# servo_receiver.net
KiCad netlist of a schematic drawn in Altium Designer
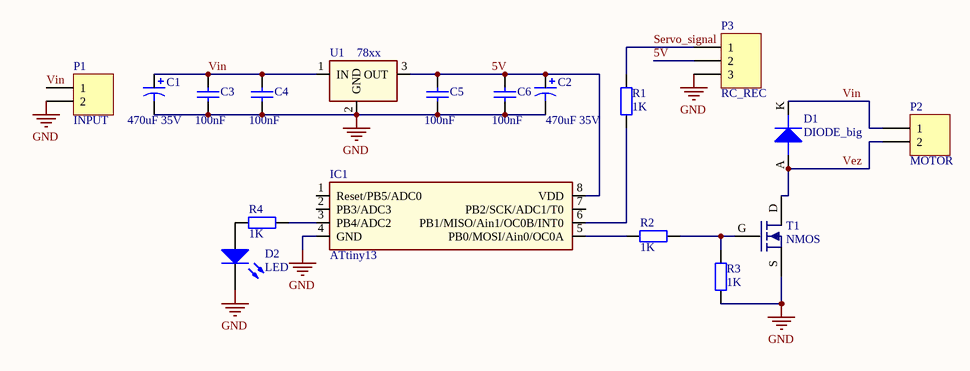
[diagram p0: servo_receiver.SchDoc]

(export (version "E")
  (design (tool "Eeschema 10.0.6"))
  (components
    (comp (ref "C1")
      (value "470uF 35V")
      (footprint "cap_10x12")
      (description "Polarized Capacitor")
      (libsource (lib "Capacitor") (part "CAP_ELECT"))
    )
    (comp (ref "C2")
      (value "470uF 35V")
      (footprint "cap_10x12")
      (description "Polarized Capacitor")
      (libsource (lib "Capacitor") (part "CAP_ELECT"))
    )
    (comp (ref "C3")
      (value "100nF")
      (footprint "FP_0805_CAP_085")
      (description "Capacitor")
      (libsource (lib "Capacitor") (part "CAP"))
    )
    (comp (ref "C4")
      (value "100nF")
      (footprint "FP_0805_CAP_085")
      (description "Capacitor")
      (libsource (lib "Capacitor") (part "CAP"))
    )
    (comp (ref "C5")
      (value "100nF")
      (footprint "FP_0805_CAP_085")
      (description "Capacitor")
      (libsource (lib "Capacitor") (part "CAP"))
    )
    (comp (ref "C6")
      (value "100nF")
      (footprint "FP_0805_CAP_085")
      (description "Capacitor")
      (libsource (lib "Capacitor") (part "CAP"))
    )
    (comp (ref "D1")
      (value "DIODE_big")
      (footprint "DO-213AB_R")
      (libsource (lib "Diode") (part "DIODE_big"))
    )
    (comp (ref "D2")
      (value "LED")
      (footprint "FP_0805_LED_RED")
      (description "Typical LED")
      (libsource (lib "Led_optical") (part "LED"))
    )
    (comp (ref "IC1") (value "ATtiny13") (footprint "WSON_n_SOIC8") (libsource (lib "uC") (part "ATtiny13")))
    (comp (ref "P1")
      (value "INPUT")
      (footprint "HDR1X2")
      (description "Header, 2-Pin")
      (fields (field (name "PUBLISHER") "Altium Limited"))
      (libsource (lib "Miscellaneous Connectors") (part "Header 2"))
    )
    (comp (ref "P2")
      (value "MOTOR")
      (footprint "HDR1X2")
      (description "Header, 2-Pin")
      (fields (field (name "PUBLISHER") "Altium Limited"))
      (libsource (lib "Miscellaneous Connectors") (part "Header 2"))
    )
    (comp (ref "P3")
      (value "RC_REC")
      (footprint "HDR1X3")
      (description "Header, 3-Pin")
      (fields (field (name "PUBLISHER") "Altium Limited"))
      (libsource (lib "Miscellaneous Connectors") (part "Header 3"))
    )
    (comp (ref "R1")
      (value "1K")
      (footprint "FP_0603_RES")
      (description "Resistor")
      (libsource (lib "Resistor") (part "RES"))
    )
    (comp (ref "R2")
      (value "1K")
      (footprint "FP_0603_RES")
      (description "Resistor")
      (libsource (lib "") (part "RES_1"))
    )
    (comp (ref "R3")
      (value "1K")
      (footprint "FP_0603_RES")
      (description "Resistor")
      (libsource (lib "Resistor") (part "RES"))
    )
    (comp (ref "R4")
      (value "1K")
      (footprint "FP_0603_RES")
      (description "Resistor")
      (libsource (lib "") (part "RES_1"))
    )
    (comp (ref "T1") (value "NMOS") (footprint "FET_SOT23") (libsource (lib "FET") (part "NMOS")))
    (comp (ref "U1") (value "78xx") (footprint "SUPPLY_D2-PAK_2") (libsource (lib "Supply") (part "78xx")))
  )
  (nets
    (net (code "1") (name "/5V") (class "Default")
      (node (ref "C2") (pin "P") (pintype "passive"))
      (node (ref "C5") (pin "1") (pinfunction "1_1") (pintype "passive"))
      (node (ref "C6") (pin "2") (pinfunction "2_2") (pintype "passive"))
      (node (ref "IC1") (pin "8") (pinfunction "VDD_8") (pintype "passive"))
      (node (ref "P3") (pin "2") (pinfunction "2_2") (pintype "passive"))
      (node (ref "U1") (pin "3") (pinfunction "OUT_3") (pintype "power_in"))
    )
    (net (code "2") (name "/Servo_signal") (class "Default")
      (node (ref "P3") (pin "1") (pinfunction "1_1") (pintype "passive"))
      (node (ref "R1") (pin "2") (pinfunction "2_2") (pintype "passive"))
    )
    (net (code "3") (name "/Vez") (class "Default")
      (node (ref "D1") (pin "A") (pinfunction "A_A") (pintype "passive"))
      (node (ref "P2") (pin "2") (pinfunction "2_2") (pintype "passive"))
      (node (ref "T1") (pin "D") (pinfunction "D_D") (pintype "passive"))
    )
    (net (code "4") (name "/Vin") (class "Default")
      (node (ref "C1") (pin "P") (pintype "passive"))
      (node (ref "C3") (pin "2") (pinfunction "2_2") (pintype "passive"))
      (node (ref "C4") (pin "2") (pinfunction "2_2") (pintype "passive"))
      (node (ref "D1") (pin "K") (pinfunction "K_K") (pintype "passive"))
      (node (ref "P1") (pin "1") (pinfunction "1_1") (pintype "passive"))
      (node (ref "P2") (pin "1") (pinfunction "1_1") (pintype "passive"))
      (node (ref "U1") (pin "1") (pinfunction "IN_1") (pintype "power_in"))
    )
    (net (code "5") (name "GND") (class "Default")
      (node (ref "C1") (pin "N") (pintype "passive"))
      (node (ref "C2") (pin "N") (pintype "passive"))
      (node (ref "C3") (pin "1") (pinfunction "1_1") (pintype "passive"))
      (node (ref "C4") (pin "1") (pinfunction "1_1") (pintype "passive"))
      (node (ref "C5") (pin "2") (pinfunction "2_2") (pintype "passive"))
      (node (ref "C6") (pin "1") (pinfunction "1_1") (pintype "passive"))
      (node (ref "D2") (pin "2") (pinfunction "K_2") (pintype "passive"))
      (node (ref "IC1") (pin "4") (pinfunction "GND_4") (pintype "passive"))
      (node (ref "P1") (pin "2") (pinfunction "2_2") (pintype "passive"))
      (node (ref "P3") (pin "3") (pinfunction "3_3") (pintype "passive"))
      (node (ref "R3") (pin "1") (pinfunction "1_1") (pintype "passive"))
      (node (ref "T1") (pin "S") (pinfunction "S_S") (pintype "passive"))
      (node (ref "U1") (pin "2") (pinfunction "GND_2") (pintype "power_in"))
    )
    (net (code "6") (name "Net-(D2-A)") (class "Default")
      (node (ref "D2") (pin "1") (pinfunction "A_1") (pintype "passive"))
      (node (ref "R4") (pin "1") (pinfunction "1_1") (pintype "passive"))
    )
    (net (code "7") (name "Net-(IC1-PB0{slash}MOSI{slash}Ain0{slash}OC0A)") (class "Default")
      (node (ref "IC1") (pin "5") (pinfunction "PB0/MOSI/Ain0/OC0A_5") (pintype "passive"))
      (node (ref "R2") (pin "1") (pinfunction "1_1") (pintype "passive"))
    )
    (net (code "8") (name "Net-(IC1-PB1{slash}MISO{slash}Ain1{slash}OC0B{slash}INT0)") (class "Default")
      (node (ref "IC1") (pin "6") (pinfunction "PB1/MISO/Ain1/OC0B/INT0_6") (pintype "passive"))
      (node (ref "R1") (pin "1") (pinfunction "1_1") (pintype "passive"))
    )
    (net (code "9") (name "Net-(IC1-PB4{slash}ADC2)") (class "Default")
      (node (ref "IC1") (pin "3") (pinfunction "PB4/ADC2_3") (pintype "passive"))
      (node (ref "R4") (pin "2") (pinfunction "2_2") (pintype "passive"))
    )
    (net (code "10") (name "Net-(R2-Pad2)") (class "Default")
      (node (ref "R2") (pin "2") (pinfunction "2_2") (pintype "passive"))
      (node (ref "R3") (pin "2") (pinfunction "2_2") (pintype "passive"))
      (node (ref "T1") (pin "G") (pinfunction "G_G") (pintype "passive"))
    )
    (net (code "11") (name "unconnected-(IC1-PB2{slash}SCK{slash}ADC1{slash}T0-Pad7)") (class "Default")
      (node (ref "IC1") (pin "7") (pinfunction "PB2/SCK/ADC1/T0_7") (pintype "passive"))
    )
    (net (code "12") (name "unconnected-(IC1-PB3{slash}ADC3-Pad2)") (class "Default")
      (node (ref "IC1") (pin "2") (pinfunction "PB3/ADC3_2") (pintype "passive"))
    )
    (net (code "13") (name "unconnected-(IC1-Reset{slash}PB5{slash}ADC0-Pad1)") (class "Default")
      (node (ref "IC1") (pin "1") (pinfunction "Reset/PB5/ADC0_1") (pintype "passive"))
    )
  )
)
